# Peripherial_Bus.net
KiCad netlist of a schematic drawn in Altium Designer
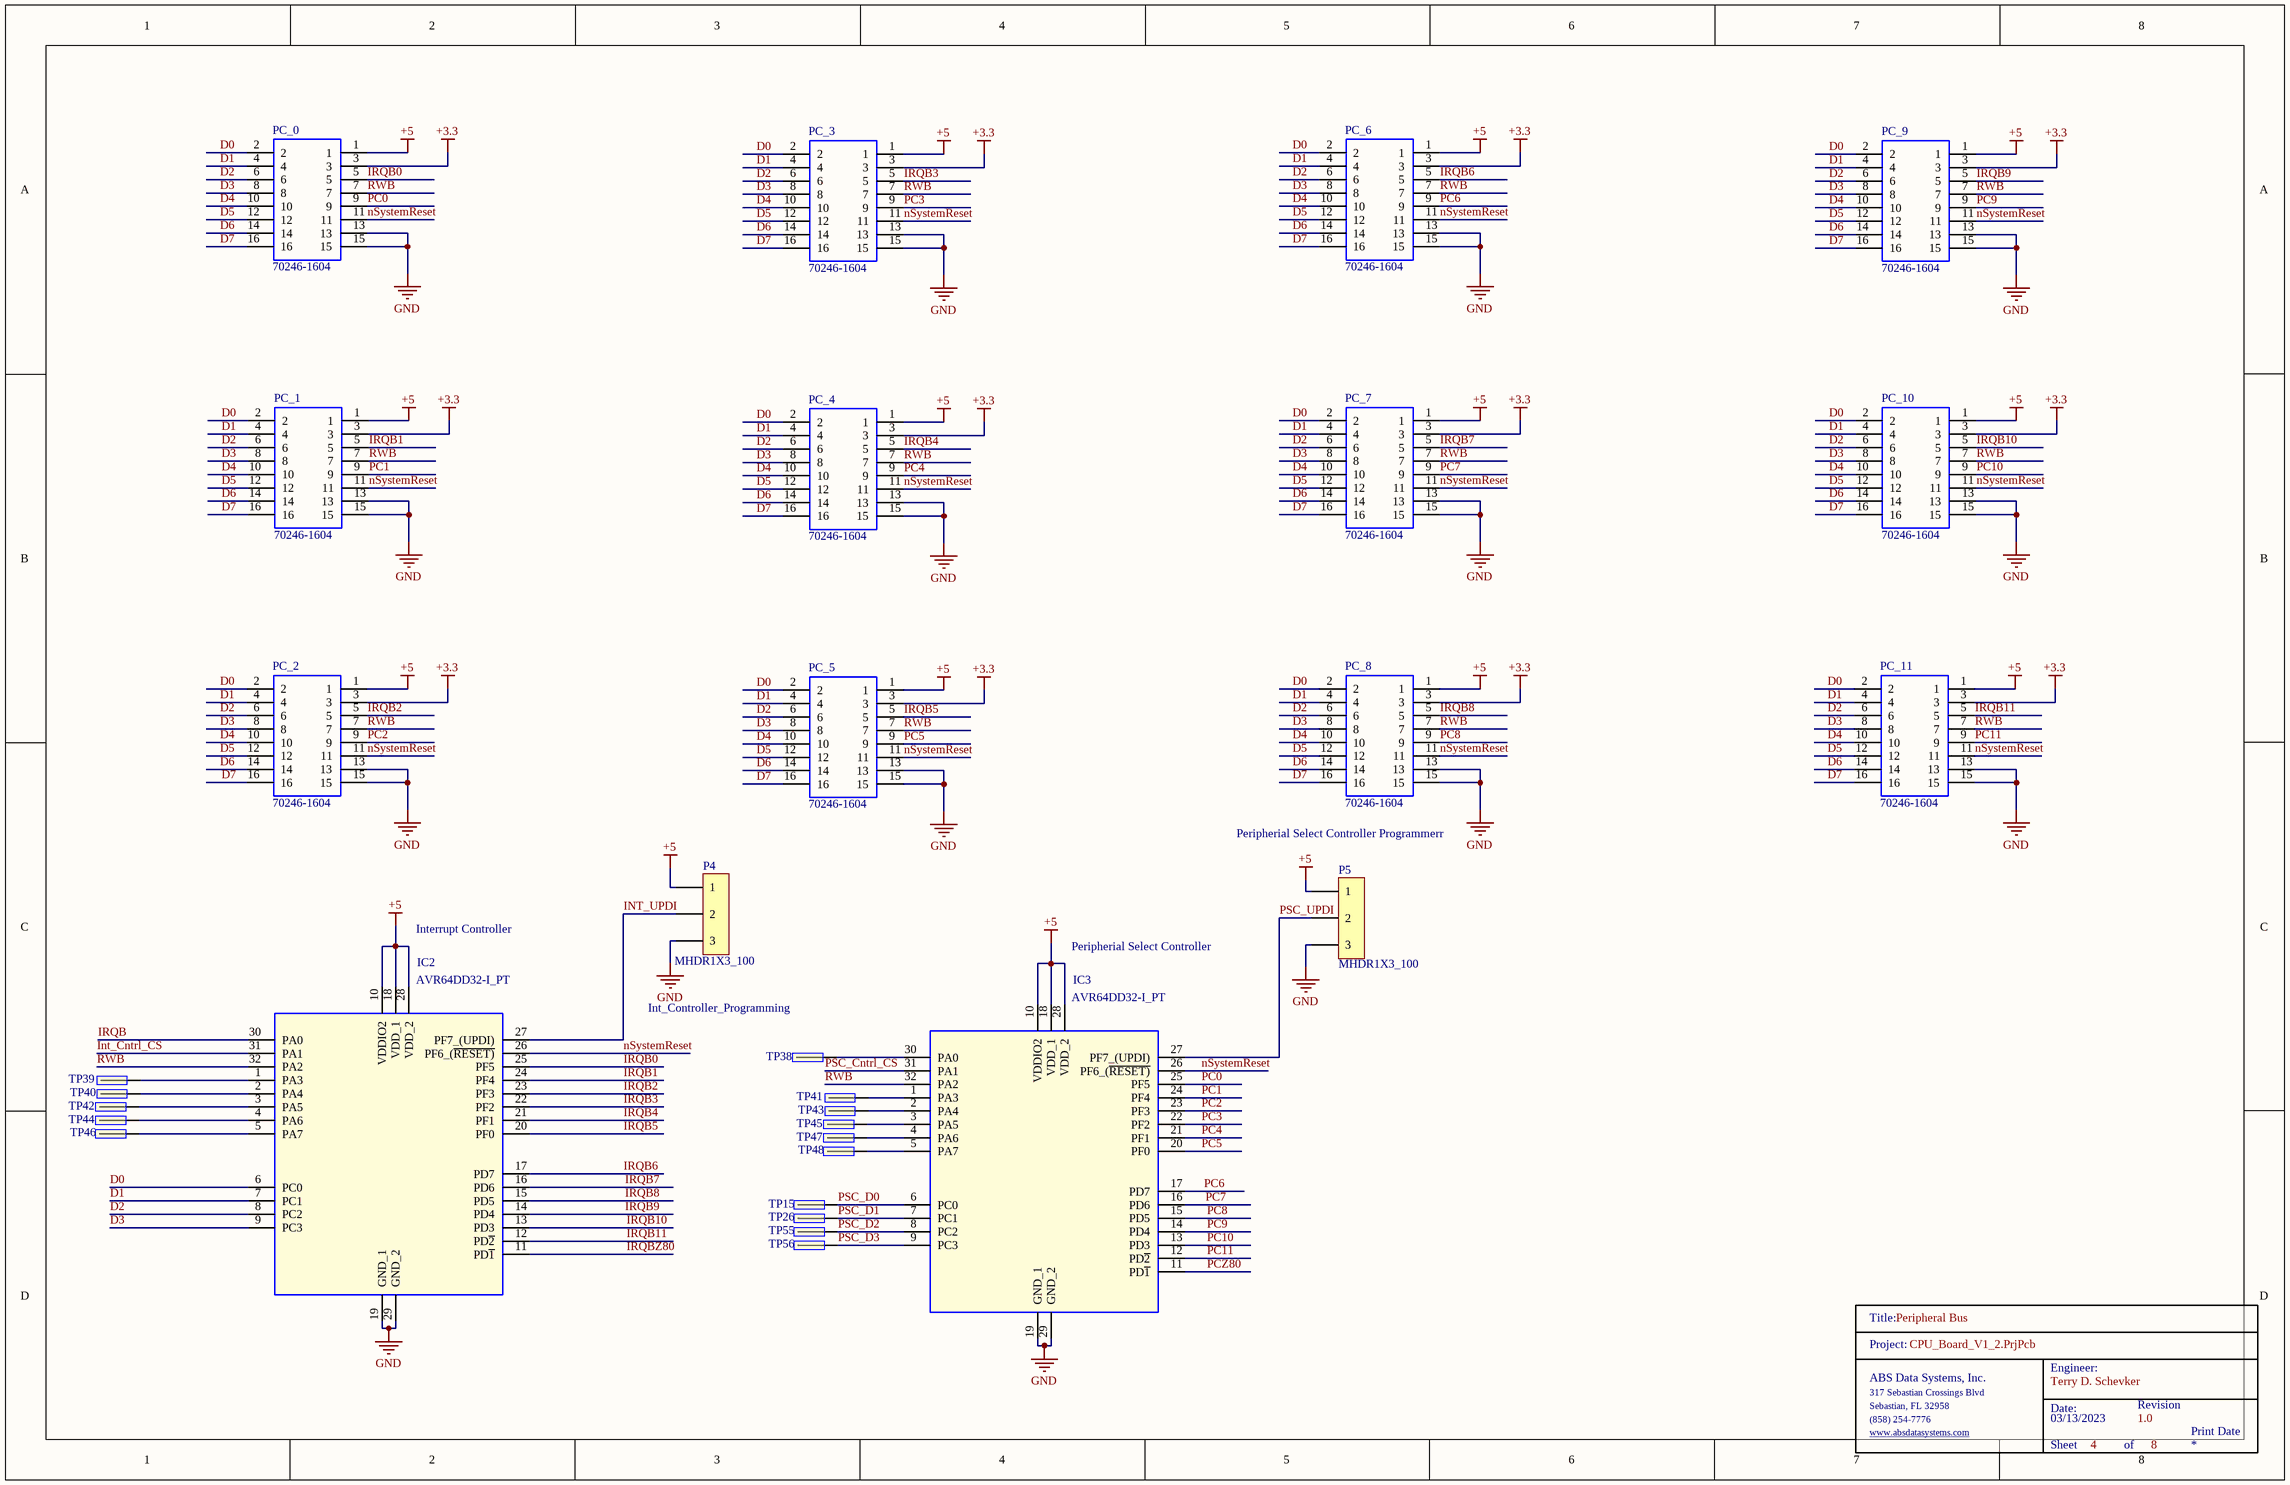
[diagram p0: Peripherial_Bus.SchDoc]

(export (version "E")
  (design (tool "Eeschema 10.0.6"))
  (components
    (comp (ref "IC2")
      (value "AVR64DD32-I_PT")
      (footprint "CPU_Memory:QFP80P900X900X120-32N")
      (description "Integrated Circuit")
      (fields (field (name "MANUFACTURER_PART_NUMBER") "AVR64DD32-I/PT ¦ MULTI-VOLTAGE I/O"))
      (libsource (lib "CPU_Memory") (part "AVR64DD32-I_PT"))
    )
    (comp (ref "IC3")
      (value "AVR64DD32-I_PT")
      (footprint "CPU_Memory:QFP80P900X900X120-32N")
      (description "Integrated Circuit")
      (fields (field (name "MANUFACTURER_PART_NUMBER") "AVR64DD32-I/PT ¦ MULTI-VOLTAGE I/O"))
      (libsource (lib "CPU_Memory") (part "AVR64DD32-I_PT"))
    )
    (comp (ref "P4")
      (value "MHDR1X3_100")
      (footprint "MHDR1X3_100")
      (description "Header, 3-Pin")
      (fields (field (name "PUBLISHER") "Altium Limited"))
      (libsource (lib "Connectors") (part "MHDR1X3_100"))
    )
    (comp (ref "P5")
      (value "MHDR1X3_100")
      (footprint "MHDR1X3_100")
      (description "Header, 3-Pin")
      (fields (field (name "PUBLISHER") "Altium Limited"))
      (libsource (lib "Connectors") (part "MHDR1X3_100"))
    )
    (comp (ref "PC_0")
      (value "70246-1604")
      (footprint "SHDR16W99P254_2X8_2794X889X927P")
      (description "Molex C-GRID 70246, 2.54mm Pitch, 16 Way, 2 Row, Straight PCB Header, Through Hole")
      (fields (field (name "MOUSER PART NUMBER") "538-70246-1604"))
      (libsource (lib "Connectors") (part "70246-1604"))
    )
    (comp (ref "PC_1")
      (value "70246-1604")
      (footprint "SHDR16W99P254_2X8_2794X889X927P")
      (description "Molex C-GRID 70246, 2.54mm Pitch, 16 Way, 2 Row, Straight PCB Header, Through Hole")
      (fields (field (name "MOUSER PART NUMBER") "538-70246-1604"))
      (libsource (lib "Connectors") (part "70246-1604"))
    )
    (comp (ref "PC_2")
      (value "70246-1604")
      (footprint "SHDR16W99P254_2X8_2794X889X927P")
      (description "Molex C-GRID 70246, 2.54mm Pitch, 16 Way, 2 Row, Straight PCB Header, Through Hole")
      (fields (field (name "MOUSER PART NUMBER") "538-70246-1604"))
      (libsource (lib "Connectors") (part "70246-1604"))
    )
    (comp (ref "PC_3")
      (value "70246-1604")
      (footprint "SHDR16W99P254_2X8_2794X889X927P")
      (description "Molex C-GRID 70246, 2.54mm Pitch, 16 Way, 2 Row, Straight PCB Header, Through Hole")
      (fields (field (name "MOUSER PART NUMBER") "538-70246-1604"))
      (libsource (lib "Connectors") (part "70246-1604"))
    )
    (comp (ref "PC_4")
      (value "70246-1604")
      (footprint "SHDR16W99P254_2X8_2794X889X927P")
      (description "Molex C-GRID 70246, 2.54mm Pitch, 16 Way, 2 Row, Straight PCB Header, Through Hole")
      (fields (field (name "MOUSER PART NUMBER") "538-70246-1604"))
      (libsource (lib "Connectors") (part "70246-1604"))
    )
    (comp (ref "PC_5")
      (value "70246-1604")
      (footprint "SHDR16W99P254_2X8_2794X889X927P")
      (description "Molex C-GRID 70246, 2.54mm Pitch, 16 Way, 2 Row, Straight PCB Header, Through Hole")
      (fields (field (name "MOUSER PART NUMBER") "538-70246-1604"))
      (libsource (lib "Connectors") (part "70246-1604"))
    )
    (comp (ref "PC_6")
      (value "70246-1604")
      (footprint "SHDR16W99P254_2X8_2794X889X927P")
      (description "Molex C-GRID 70246, 2.54mm Pitch, 16 Way, 2 Row, Straight PCB Header, Through Hole")
      (fields (field (name "MOUSER PART NUMBER") "538-70246-1604"))
      (libsource (lib "Connectors") (part "70246-1604"))
    )
    (comp (ref "PC_7")
      (value "70246-1604")
      (footprint "SHDR16W99P254_2X8_2794X889X927P")
      (description "Molex C-GRID 70246, 2.54mm Pitch, 16 Way, 2 Row, Straight PCB Header, Through Hole")
      (fields (field (name "MOUSER PART NUMBER") "538-70246-1604"))
      (libsource (lib "Connectors") (part "70246-1604"))
    )
    (comp (ref "PC_8")
      (value "70246-1604")
      (footprint "SHDR16W99P254_2X8_2794X889X927P")
      (description "Molex C-GRID 70246, 2.54mm Pitch, 16 Way, 2 Row, Straight PCB Header, Through Hole")
      (fields (field (name "MOUSER PART NUMBER") "538-70246-1604"))
      (libsource (lib "Connectors") (part "70246-1604"))
    )
    (comp (ref "PC_9")
      (value "70246-1604")
      (footprint "SHDR16W99P254_2X8_2794X889X927P")
      (description "Molex C-GRID 70246, 2.54mm Pitch, 16 Way, 2 Row, Straight PCB Header, Through Hole")
      (fields (field (name "MOUSER PART NUMBER") "538-70246-1604"))
      (libsource (lib "Connectors") (part "70246-1604"))
    )
    (comp (ref "PC_10")
      (value "70246-1604")
      (footprint "SHDR16W99P254_2X8_2794X889X927P")
      (description "Molex C-GRID 70246, 2.54mm Pitch, 16 Way, 2 Row, Straight PCB Header, Through Hole")
      (fields (field (name "MOUSER PART NUMBER") "538-70246-1604"))
      (libsource (lib "Connectors") (part "70246-1604"))
    )
    (comp (ref "PC_11")
      (value "70246-1604")
      (footprint "SHDR16W99P254_2X8_2794X889X927P")
      (description "Molex C-GRID 70246, 2.54mm Pitch, 16 Way, 2 Row, Straight PCB Header, Through Hole")
      (fields (field (name "MOUSER PART NUMBER") "538-70246-1604"))
      (libsource (lib "Connectors") (part "70246-1604"))
    )
    (comp (ref "TP15")
      (value "TP")
      (footprint "TP")
      (fields
        (field (name "MANUFACTURER") "Samtec")
        (field (name "MANUFACTURER PART NUMBER") "TST-105-01-G-D")
      )
      (libsource (lib "Misc") (part "TP"))
    )
    (comp (ref "TP26")
      (value "TP")
      (footprint "TP")
      (fields
        (field (name "MANUFACTURER") "Samtec")
        (field (name "MANUFACTURER PART NUMBER") "TST-105-01-G-D")
      )
      (libsource (lib "Misc") (part "TP"))
    )
    (comp (ref "TP38")
      (value "TP")
      (footprint "TP")
      (fields
        (field (name "MANUFACTURER") "Samtec")
        (field (name "MANUFACTURER PART NUMBER") "TST-105-01-G-D")
      )
      (libsource (lib "Misc") (part "TP"))
    )
    (comp (ref "TP39")
      (value "TP")
      (footprint "TP")
      (fields
        (field (name "MANUFACTURER") "Samtec")
        (field (name "MANUFACTURER PART NUMBER") "TST-105-01-G-D")
      )
      (libsource (lib "Misc") (part "TP"))
    )
    (comp (ref "TP40")
      (value "TP")
      (footprint "TP")
      (fields
        (field (name "MANUFACTURER") "Samtec")
        (field (name "MANUFACTURER PART NUMBER") "TST-105-01-G-D")
      )
      (libsource (lib "Misc") (part "TP"))
    )
    (comp (ref "TP41")
      (value "TP")
      (footprint "TP")
      (fields
        (field (name "MANUFACTURER") "Samtec")
        (field (name "MANUFACTURER PART NUMBER") "TST-105-01-G-D")
      )
      (libsource (lib "Misc") (part "TP"))
    )
    (comp (ref "TP42")
      (value "TP")
      (footprint "TP")
      (fields
        (field (name "MANUFACTURER") "Samtec")
        (field (name "MANUFACTURER PART NUMBER") "TST-105-01-G-D")
      )
      (libsource (lib "Misc") (part "TP"))
    )
    (comp (ref "TP43")
      (value "TP")
      (footprint "TP")
      (fields
        (field (name "MANUFACTURER") "Samtec")
        (field (name "MANUFACTURER PART NUMBER") "TST-105-01-G-D")
      )
      (libsource (lib "Misc") (part "TP"))
    )
    (comp (ref "TP44")
      (value "TP")
      (footprint "TP")
      (fields
        (field (name "MANUFACTURER") "Samtec")
        (field (name "MANUFACTURER PART NUMBER") "TST-105-01-G-D")
      )
      (libsource (lib "Misc") (part "TP"))
    )
    (comp (ref "TP45")
      (value "TP")
      (footprint "TP")
      (fields
        (field (name "MANUFACTURER") "Samtec")
        (field (name "MANUFACTURER PART NUMBER") "TST-105-01-G-D")
      )
      (libsource (lib "Misc") (part "TP"))
    )
    (comp (ref "TP46")
      (value "TP")
      (footprint "TP")
      (fields
        (field (name "MANUFACTURER") "Samtec")
        (field (name "MANUFACTURER PART NUMBER") "TST-105-01-G-D")
      )
      (libsource (lib "Misc") (part "TP"))
    )
    (comp (ref "TP47")
      (value "TP")
      (footprint "TP")
      (fields
        (field (name "MANUFACTURER") "Samtec")
        (field (name "MANUFACTURER PART NUMBER") "TST-105-01-G-D")
      )
      (libsource (lib "Misc") (part "TP"))
    )
    (comp (ref "TP48")
      (value "TP")
      (footprint "TP")
      (fields
        (field (name "MANUFACTURER") "Samtec")
        (field (name "MANUFACTURER PART NUMBER") "TST-105-01-G-D")
      )
      (libsource (lib "Misc") (part "TP"))
    )
    (comp (ref "TP55")
      (value "TP")
      (footprint "TP")
      (fields
        (field (name "MANUFACTURER") "Samtec")
        (field (name "MANUFACTURER PART NUMBER") "TST-105-01-G-D")
      )
      (libsource (lib "Misc") (part "TP"))
    )
    (comp (ref "TP56")
      (value "TP")
      (footprint "TP")
      (fields
        (field (name "MANUFACTURER") "Samtec")
        (field (name "MANUFACTURER PART NUMBER") "TST-105-01-G-D")
      )
      (libsource (lib "Misc") (part "TP"))
    )
  )
  (nets
    (net (code "1") (name "+3.3") (class "Default")
      (node (ref "PC_0") (pin "3") (pinfunction "3_3") (pintype "passive"))
      (node (ref "PC_1") (pin "3") (pinfunction "3_3") (pintype "passive"))
      (node (ref "PC_10") (pin "3") (pinfunction "3_3") (pintype "passive"))
      (node (ref "PC_11") (pin "3") (pinfunction "3_3") (pintype "passive"))
      (node (ref "PC_2") (pin "3") (pinfunction "3_3") (pintype "passive"))
      (node (ref "PC_3") (pin "3") (pinfunction "3_3") (pintype "passive"))
      (node (ref "PC_4") (pin "3") (pinfunction "3_3") (pintype "passive"))
      (node (ref "PC_5") (pin "3") (pinfunction "3_3") (pintype "passive"))
      (node (ref "PC_6") (pin "3") (pinfunction "3_3") (pintype "passive"))
      (node (ref "PC_7") (pin "3") (pinfunction "3_3") (pintype "passive"))
      (node (ref "PC_8") (pin "3") (pinfunction "3_3") (pintype "passive"))
      (node (ref "PC_9") (pin "3") (pinfunction "3_3") (pintype "passive"))
    )
    (net (code "2") (name "+5") (class "Default")
      (node (ref "IC2") (pin "10") (pinfunction "VDDIO2_10") (pintype "passive"))
      (node (ref "IC2") (pin "18") (pinfunction "VDD_1_18") (pintype "passive"))
      (node (ref "IC2") (pin "28") (pinfunction "VDD_2_28") (pintype "passive"))
      (node (ref "IC3") (pin "10") (pinfunction "VDDIO2_10") (pintype "passive"))
      (node (ref "IC3") (pin "18") (pinfunction "VDD_1_18") (pintype "passive"))
      (node (ref "IC3") (pin "28") (pinfunction "VDD_2_28") (pintype "passive"))
      (node (ref "P4") (pin "1") (pinfunction "1_1") (pintype "passive"))
      (node (ref "P5") (pin "1") (pinfunction "1_1") (pintype "passive"))
      (node (ref "PC_0") (pin "1") (pinfunction "1_1") (pintype "passive"))
      (node (ref "PC_1") (pin "1") (pinfunction "1_1") (pintype "passive"))
      (node (ref "PC_10") (pin "1") (pinfunction "1_1") (pintype "passive"))
      (node (ref "PC_11") (pin "1") (pinfunction "1_1") (pintype "passive"))
      (node (ref "PC_2") (pin "1") (pinfunction "1_1") (pintype "passive"))
      (node (ref "PC_3") (pin "1") (pinfunction "1_1") (pintype "passive"))
      (node (ref "PC_4") (pin "1") (pinfunction "1_1") (pintype "passive"))
      (node (ref "PC_5") (pin "1") (pinfunction "1_1") (pintype "passive"))
      (node (ref "PC_6") (pin "1") (pinfunction "1_1") (pintype "passive"))
      (node (ref "PC_7") (pin "1") (pinfunction "1_1") (pintype "passive"))
      (node (ref "PC_8") (pin "1") (pinfunction "1_1") (pintype "passive"))
      (node (ref "PC_9") (pin "1") (pinfunction "1_1") (pintype "passive"))
    )
    (net (code "3") (name "/D0") (class "Default")
      (node (ref "IC2") (pin "6") (pinfunction "PC0_6") (pintype "passive"))
      (node (ref "PC_0") (pin "2") (pinfunction "2_2") (pintype "passive"))
      (node (ref "PC_1") (pin "2") (pinfunction "2_2") (pintype "passive"))
      (node (ref "PC_10") (pin "2") (pinfunction "2_2") (pintype "passive"))
      (node (ref "PC_11") (pin "2") (pinfunction "2_2") (pintype "passive"))
      (node (ref "PC_2") (pin "2") (pinfunction "2_2") (pintype "passive"))
      (node (ref "PC_3") (pin "2") (pinfunction "2_2") (pintype "passive"))
      (node (ref "PC_4") (pin "2") (pinfunction "2_2") (pintype "passive"))
      (node (ref "PC_5") (pin "2") (pinfunction "2_2") (pintype "passive"))
      (node (ref "PC_6") (pin "2") (pinfunction "2_2") (pintype "passive"))
      (node (ref "PC_7") (pin "2") (pinfunction "2_2") (pintype "passive"))
      (node (ref "PC_8") (pin "2") (pinfunction "2_2") (pintype "passive"))
      (node (ref "PC_9") (pin "2") (pinfunction "2_2") (pintype "passive"))
    )
    (net (code "4") (name "/D1") (class "Default")
      (node (ref "IC2") (pin "7") (pinfunction "PC1_7") (pintype "passive"))
      (node (ref "PC_0") (pin "4") (pinfunction "4_4") (pintype "passive"))
      (node (ref "PC_1") (pin "4") (pinfunction "4_4") (pintype "passive"))
      (node (ref "PC_10") (pin "4") (pinfunction "4_4") (pintype "passive"))
      (node (ref "PC_11") (pin "4") (pinfunction "4_4") (pintype "passive"))
      (node (ref "PC_2") (pin "4") (pinfunction "4_4") (pintype "passive"))
      (node (ref "PC_3") (pin "4") (pinfunction "4_4") (pintype "passive"))
      (node (ref "PC_4") (pin "4") (pinfunction "4_4") (pintype "passive"))
      (node (ref "PC_5") (pin "4") (pinfunction "4_4") (pintype "passive"))
      (node (ref "PC_6") (pin "4") (pinfunction "4_4") (pintype "passive"))
      (node (ref "PC_7") (pin "4") (pinfunction "4_4") (pintype "passive"))
      (node (ref "PC_8") (pin "4") (pinfunction "4_4") (pintype "passive"))
      (node (ref "PC_9") (pin "4") (pinfunction "4_4") (pintype "passive"))
    )
    (net (code "5") (name "/D2") (class "Default")
      (node (ref "IC2") (pin "8") (pinfunction "PC2_8") (pintype "passive"))
      (node (ref "PC_0") (pin "6") (pinfunction "6_6") (pintype "passive"))
      (node (ref "PC_1") (pin "6") (pinfunction "6_6") (pintype "passive"))
      (node (ref "PC_10") (pin "6") (pinfunction "6_6") (pintype "passive"))
      (node (ref "PC_11") (pin "6") (pinfunction "6_6") (pintype "passive"))
      (node (ref "PC_2") (pin "6") (pinfunction "6_6") (pintype "passive"))
      (node (ref "PC_3") (pin "6") (pinfunction "6_6") (pintype "passive"))
      (node (ref "PC_4") (pin "6") (pinfunction "6_6") (pintype "passive"))
      (node (ref "PC_5") (pin "6") (pinfunction "6_6") (pintype "passive"))
      (node (ref "PC_6") (pin "6") (pinfunction "6_6") (pintype "passive"))
      (node (ref "PC_7") (pin "6") (pinfunction "6_6") (pintype "passive"))
      (node (ref "PC_8") (pin "6") (pinfunction "6_6") (pintype "passive"))
      (node (ref "PC_9") (pin "6") (pinfunction "6_6") (pintype "passive"))
    )
    (net (code "6") (name "/D3") (class "Default")
      (node (ref "IC2") (pin "9") (pinfunction "PC3_9") (pintype "passive"))
      (node (ref "PC_0") (pin "8") (pinfunction "8_8") (pintype "passive"))
      (node (ref "PC_1") (pin "8") (pinfunction "8_8") (pintype "passive"))
      (node (ref "PC_10") (pin "8") (pinfunction "8_8") (pintype "passive"))
      (node (ref "PC_11") (pin "8") (pinfunction "8_8") (pintype "passive"))
      (node (ref "PC_2") (pin "8") (pinfunction "8_8") (pintype "passive"))
      (node (ref "PC_3") (pin "8") (pinfunction "8_8") (pintype "passive"))
      (node (ref "PC_4") (pin "8") (pinfunction "8_8") (pintype "passive"))
      (node (ref "PC_5") (pin "8") (pinfunction "8_8") (pintype "passive"))
      (node (ref "PC_6") (pin "8") (pinfunction "8_8") (pintype "passive"))
      (node (ref "PC_7") (pin "8") (pinfunction "8_8") (pintype "passive"))
      (node (ref "PC_8") (pin "8") (pinfunction "8_8") (pintype "passive"))
      (node (ref "PC_9") (pin "8") (pinfunction "8_8") (pintype "passive"))
    )
    (net (code "7") (name "/D4") (class "Default")
      (node (ref "PC_0") (pin "10") (pinfunction "10_10") (pintype "passive"))
      (node (ref "PC_1") (pin "10") (pinfunction "10_10") (pintype "passive"))
      (node (ref "PC_10") (pin "10") (pinfunction "10_10") (pintype "passive"))
      (node (ref "PC_11") (pin "10") (pinfunction "10_10") (pintype "passive"))
      (node (ref "PC_2") (pin "10") (pinfunction "10_10") (pintype "passive"))
      (node (ref "PC_3") (pin "10") (pinfunction "10_10") (pintype "passive"))
      (node (ref "PC_4") (pin "10") (pinfunction "10_10") (pintype "passive"))
      (node (ref "PC_5") (pin "10") (pinfunction "10_10") (pintype "passive"))
      (node (ref "PC_6") (pin "10") (pinfunction "10_10") (pintype "passive"))
      (node (ref "PC_7") (pin "10") (pinfunction "10_10") (pintype "passive"))
      (node (ref "PC_8") (pin "10") (pinfunction "10_10") (pintype "passive"))
      (node (ref "PC_9") (pin "10") (pinfunction "10_10") (pintype "passive"))
    )
    (net (code "8") (name "/D5") (class "Default")
      (node (ref "PC_0") (pin "12") (pinfunction "12_12") (pintype "passive"))
      (node (ref "PC_1") (pin "12") (pinfunction "12_12") (pintype "passive"))
      (node (ref "PC_10") (pin "12") (pinfunction "12_12") (pintype "passive"))
      (node (ref "PC_11") (pin "12") (pinfunction "12_12") (pintype "passive"))
      (node (ref "PC_2") (pin "12") (pinfunction "12_12") (pintype "passive"))
      (node (ref "PC_3") (pin "12") (pinfunction "12_12") (pintype "passive"))
      (node (ref "PC_4") (pin "12") (pinfunction "12_12") (pintype "passive"))
      (node (ref "PC_5") (pin "12") (pinfunction "12_12") (pintype "passive"))
      (node (ref "PC_6") (pin "12") (pinfunction "12_12") (pintype "passive"))
      (node (ref "PC_7") (pin "12") (pinfunction "12_12") (pintype "passive"))
      (node (ref "PC_8") (pin "12") (pinfunction "12_12") (pintype "passive"))
      (node (ref "PC_9") (pin "12") (pinfunction "12_12") (pintype "passive"))
    )
    (net (code "9") (name "/D6") (class "Default")
      (node (ref "PC_0") (pin "14") (pinfunction "14_14") (pintype "passive"))
      (node (ref "PC_1") (pin "14") (pinfunction "14_14") (pintype "passive"))
      (node (ref "PC_10") (pin "14") (pinfunction "14_14") (pintype "passive"))
      (node (ref "PC_11") (pin "14") (pinfunction "14_14") (pintype "passive"))
      (node (ref "PC_2") (pin "14") (pinfunction "14_14") (pintype "passive"))
      (node (ref "PC_3") (pin "14") (pinfunction "14_14") (pintype "passive"))
      (node (ref "PC_4") (pin "14") (pinfunction "14_14") (pintype "passive"))
      (node (ref "PC_5") (pin "14") (pinfunction "14_14") (pintype "passive"))
      (node (ref "PC_6") (pin "14") (pinfunction "14_14") (pintype "passive"))
      (node (ref "PC_7") (pin "14") (pinfunction "14_14") (pintype "passive"))
      (node (ref "PC_8") (pin "14") (pinfunction "14_14") (pintype "passive"))
      (node (ref "PC_9") (pin "14") (pinfunction "14_14") (pintype "passive"))
    )
    (net (code "10") (name "/D7") (class "Default")
      (node (ref "PC_0") (pin "16") (pinfunction "16_16") (pintype "passive"))
      (node (ref "PC_1") (pin "16") (pinfunction "16_16") (pintype "passive"))
      (node (ref "PC_10") (pin "16") (pinfunction "16_16") (pintype "passive"))
      (node (ref "PC_11") (pin "16") (pinfunction "16_16") (pintype "passive"))
      (node (ref "PC_2") (pin "16") (pinfunction "16_16") (pintype "passive"))
      (node (ref "PC_3") (pin "16") (pinfunction "16_16") (pintype "passive"))
      (node (ref "PC_4") (pin "16") (pinfunction "16_16") (pintype "passive"))
      (node (ref "PC_5") (pin "16") (pinfunction "16_16") (pintype "passive"))
      (node (ref "PC_6") (pin "16") (pinfunction "16_16") (pintype "passive"))
      (node (ref "PC_7") (pin "16") (pinfunction "16_16") (pintype "passive"))
      (node (ref "PC_8") (pin "16") (pinfunction "16_16") (pintype "passive"))
      (node (ref "PC_9") (pin "16") (pinfunction "16_16") (pintype "passive"))
    )
    (net (code "11") (name "/INT_UPDI") (class "Default")
      (node (ref "IC2") (pin "27") (pinfunction "PF7_(UPDI)_27") (pintype "passive"))
      (node (ref "P4") (pin "2") (pinfunction "2_2") (pintype "passive"))
    )
    (net (code "12") (name "/IRQB") (class "Default")
      (node (ref "IC2") (pin "30") (pinfunction "PA0_30") (pintype "passive"))
    )
    (net (code "13") (name "/IRQB0") (class "Default")
      (node (ref "IC2") (pin "25") (pinfunction "PF5_25") (pintype "passive"))
      (node (ref "PC_0") (pin "5") (pinfunction "5_5") (pintype "passive"))
    )
    (net (code "14") (name "/IRQB1") (class "Default")
      (node (ref "IC2") (pin "24") (pinfunction "PF4_24") (pintype "passive"))
      (node (ref "PC_1") (pin "5") (pinfunction "5_5") (pintype "passive"))
    )
    (net (code "15") (name "/IRQB2") (class "Default")
      (node (ref "IC2") (pin "23") (pinfunction "PF3_23") (pintype "passive"))
      (node (ref "PC_2") (pin "5") (pinfunction "5_5") (pintype "passive"))
    )
    (net (code "16") (name "/IRQB3") (class "Default")
      (node (ref "IC2") (pin "22") (pinfunction "PF2_22") (pintype "passive"))
      (node (ref "PC_3") (pin "5") (pinfunction "5_5") (pintype "passive"))
    )
    (net (code "17") (name "/IRQB4") (class "Default")
      (node (ref "IC2") (pin "21") (pinfunction "PF1_21") (pintype "passive"))
      (node (ref "PC_4") (pin "5") (pinfunction "5_5") (pintype "passive"))
    )
    (net (code "18") (name "/IRQB5") (class "Default")
      (node (ref "IC2") (pin "20") (pinfunction "PF0_20") (pintype "passive"))
      (node (ref "PC_5") (pin "5") (pinfunction "5_5") (pintype "passive"))
    )
    (net (code "19") (name "/IRQB6") (class "Default")
      (node (ref "IC2") (pin "17") (pinfunction "PD7_17") (pintype "passive"))
      (node (ref "PC_6") (pin "5") (pinfunction "5_5") (pintype "passive"))
    )
    (net (code "20") (name "/IRQB7") (class "Default")
      (node (ref "IC2") (pin "16") (pinfunction "PD6_16") (pintype "passive"))
      (node (ref "PC_7") (pin "5") (pinfunction "5_5") (pintype "passive"))
    )
    (net (code "21") (name "/IRQB8") (class "Default")
      (node (ref "IC2") (pin "15") (pinfunction "PD5_15") (pintype "passive"))
      (node (ref "PC_8") (pin "5") (pinfunction "5_5") (pintype "passive"))
    )
    (net (code "22") (name "/IRQB9") (class "Default")
      (node (ref "IC2") (pin "14") (pinfunction "PD4_14") (pintype "passive"))
      (node (ref "PC_9") (pin "5") (pinfunction "5_5") (pintype "passive"))
    )
    (net (code "23") (name "/IRQB10") (class "Default")
      (node (ref "IC2") (pin "13") (pinfunction "PD3_13") (pintype "passive"))
      (node (ref "PC_10") (pin "5") (pinfunction "5_5") (pintype "passive"))
    )
    (net (code "24") (name "/IRQB11") (class "Default")
      (node (ref "IC2") (pin "12") (pinfunction "PD~{2}_12") (pintype "passive"))
      (node (ref "PC_11") (pin "5") (pinfunction "5_5") (pintype "passive"))
    )
    (net (code "25") (name "/IRQBZ80") (class "Default")
      (node (ref "IC2") (pin "11") (pinfunction "PD~{1}_11") (pintype "passive"))
    )
    (net (code "26") (name "/Int_Cntrl_CS") (class "Default")
      (node (ref "IC2") (pin "31") (pinfunction "PA1_31") (pintype "passive"))
    )
    (net (code "27") (name "/PC0") (class "Default")
      (node (ref "IC3") (pin "25") (pinfunction "PF5_25") (pintype "passive"))
      (node (ref "PC_0") (pin "9") (pinfunction "9_9") (pintype "passive"))
    )
    (net (code "28") (name "/PC1") (class "Default")
      (node (ref "IC3") (pin "24") (pinfunction "PF4_24") (pintype "passive"))
      (node (ref "PC_1") (pin "9") (pinfunction "9_9") (pintype "passive"))
    )
    (net (code "29") (name "/PC2") (class "Default")
      (node (ref "IC3") (pin "23") (pinfunction "PF3_23") (pintype "passive"))
      (node (ref "PC_2") (pin "9") (pinfunction "9_9") (pintype "passive"))
    )
    (net (code "30") (name "/PC3") (class "Default")
      (node (ref "IC3") (pin "22") (pinfunction "PF2_22") (pintype "passive"))
      (node (ref "PC_3") (pin "9") (pinfunction "9_9") (pintype "passive"))
    )
    (net (code "31") (name "/PC4") (class "Default")
      (node (ref "IC3") (pin "21") (pinfunction "PF1_21") (pintype "passive"))
      (node (ref "PC_4") (pin "9") (pinfunction "9_9") (pintype "passive"))
    )
    (net (code "32") (name "/PC5") (class "Default")
      (node (ref "IC3") (pin "20") (pinfunction "PF0_20") (pintype "passive"))
      (node (ref "PC_5") (pin "9") (pinfunction "9_9") (pintype "passive"))
    )
    (net (code "33") (name "/PC6") (class "Default")
      (node (ref "IC3") (pin "17") (pinfunction "PD7_17") (pintype "passive"))
      (node (ref "PC_6") (pin "9") (pinfunction "9_9") (pintype "passive"))
    )
    (net (code "34") (name "/PC7") (class "Default")
      (node (ref "IC3") (pin "16") (pinfunction "PD6_16") (pintype "passive"))
      (node (ref "PC_7") (pin "9") (pinfunction "9_9") (pintype "passive"))
    )
    (net (code "35") (name "/PC8") (class "Default")
      (node (ref "IC3") (pin "15") (pinfunction "PD5_15") (pintype "passive"))
      (node (ref "PC_8") (pin "9") (pinfunction "9_9") (pintype "passive"))
    )
    (net (code "36") (name "/PC9") (class "Default")
      (node (ref "IC3") (pin "14") (pinfunction "PD4_14") (pintype "passive"))
      (node (ref "PC_9") (pin "9") (pinfunction "9_9") (pintype "passive"))
    )
    (net (code "37") (name "/PC10") (class "Default")
      (node (ref "IC3") (pin "13") (pinfunction "PD3_13") (pintype "passive"))
      (node (ref "PC_10") (pin "9") (pinfunction "9_9") (pintype "passive"))
    )
    (net (code "38") (name "/PC11") (class "Default")
      (node (ref "IC3") (pin "12") (pinfunction "PD~{2}_12") (pintype "passive"))
      (node (ref "PC_11") (pin "9") (pinfunction "9_9") (pintype "passive"))
    )
    (net (code "39") (name "/PCZ80") (class "Default")
      (node (ref "IC3") (pin "11") (pinfunction "PD~{1}_11") (pintype "passive"))
    )
    (net (code "40") (name "/PSC_Cntrl_CS") (class "Default")
      (node (ref "IC3") (pin "31") (pinfunction "PA1_31") (pintype "passive"))
    )
    (net (code "41") (name "/PSC_D0") (class "Default")
      (node (ref "IC3") (pin "6") (pinfunction "PC0_6") (pintype "passive"))
      (node (ref "TP15") (pin "1") (pinfunction "1_1") (pintype "passive"))
    )
    (net (code "42") (name "/PSC_D1") (class "Default")
      (node (ref "IC3") (pin "7") (pinfunction "PC1_7") (pintype "passive"))
      (node (ref "TP26") (pin "1") (pinfunction "1_1") (pintype "passive"))
    )
    (net (code "43") (name "/PSC_D2") (class "Default")
      (node (ref "IC3") (pin "8") (pinfunction "PC2_8") (pintype "passive"))
      (node (ref "TP55") (pin "1") (pinfunction "1_1") (pintype "passive"))
    )
    (net (code "44") (name "/PSC_D3") (class "Default")
      (node (ref "IC3") (pin "9") (pinfunction "PC3_9") (pintype "passive"))
      (node (ref "TP56") (pin "1") (pinfunction "1_1") (pintype "passive"))
    )
    (net (code "45") (name "/PSC_UPDI") (class "Default")
      (node (ref "IC3") (pin "27") (pinfunction "PF7_(UPDI)_27") (pintype "passive"))
      (node (ref "P5") (pin "2") (pinfunction "2_2") (pintype "passive"))
    )
    (net (code "46") (name "/RWB") (class "Default")
      (node (ref "IC2") (pin "32") (pinfunction "PA2_32") (pintype "passive"))
      (node (ref "IC3") (pin "32") (pinfunction "PA2_32") (pintype "passive"))
      (node (ref "PC_0") (pin "7") (pinfunction "7_7") (pintype "passive"))
      (node (ref "PC_1") (pin "7") (pinfunction "7_7") (pintype "passive"))
      (node (ref "PC_10") (pin "7") (pinfunction "7_7") (pintype "passive"))
      (node (ref "PC_11") (pin "7") (pinfunction "7_7") (pintype "passive"))
      (node (ref "PC_2") (pin "7") (pinfunction "7_7") (pintype "passive"))
      (node (ref "PC_3") (pin "7") (pinfunction "7_7") (pintype "passive"))
      (node (ref "PC_4") (pin "7") (pinfunction "7_7") (pintype "passive"))
      (node (ref "PC_5") (pin "7") (pinfunction "7_7") (pintype "passive"))
      (node (ref "PC_6") (pin "7") (pinfunction "7_7") (pintype "passive"))
      (node (ref "PC_7") (pin "7") (pinfunction "7_7") (pintype "passive"))
      (node (ref "PC_8") (pin "7") (pinfunction "7_7") (pintype "passive"))
      (node (ref "PC_9") (pin "7") (pinfunction "7_7") (pintype "passive"))
    )
    (net (code "47") (name "/nSystemReset") (class "Default")
      (node (ref "IC2") (pin "26") (pinfunction "PF6_(~{RESET)}_26") (pintype "passive"))
      (node (ref "IC3") (pin "26") (pinfunction "PF6_(~{RESET)}_26") (pintype "passive"))
      (node (ref "PC_0") (pin "11") (pinfunction "11_11") (pintype "passive"))
      (node (ref "PC_1") (pin "11") (pinfunction "11_11") (pintype "passive"))
      (node (ref "PC_10") (pin "11") (pinfunction "11_11") (pintype "passive"))
      (node (ref "PC_11") (pin "11") (pinfunction "11_11") (pintype "passive"))
      (node (ref "PC_2") (pin "11") (pinfunction "11_11") (pintype "passive"))
      (node (ref "PC_3") (pin "11") (pinfunction "11_11") (pintype "passive"))
      (node (ref "PC_4") (pin "11") (pinfunction "11_11") (pintype "passive"))
      (node (ref "PC_5") (pin "11") (pinfunction "11_11") (pintype "passive"))
      (node (ref "PC_6") (pin "11") (pinfunction "11_11") (pintype "passive"))
      (node (ref "PC_7") (pin "11") (pinfunction "11_11") (pintype "passive"))
      (node (ref "PC_8") (pin "11") (pinfunction "11_11") (pintype "passive"))
      (node (ref "PC_9") (pin "11") (pinfunction "11_11") (pintype "passive"))
    )
    (net (code "48") (name "GND") (class "Default")
      (node (ref "IC2") (pin "19") (pinfunction "GND_1_19") (pintype "passive"))
      (node (ref "IC2") (pin "29") (pinfunction "GND_2_29") (pintype "passive"))
      (node (ref "IC3") (pin "19") (pinfunction "GND_1_19") (pintype "passive"))
      (node (ref "IC3") (pin "29") (pinfunction "GND_2_29") (pintype "passive"))
      (node (ref "P4") (pin "3") (pinfunction "3_3") (pintype "passive"))
      (node (ref "P5") (pin "3") (pinfunction "3_3") (pintype "passive"))
      (node (ref "PC_0") (pin "13") (pinfunction "13_13") (pintype "passive"))
      (node (ref "PC_0") (pin "15") (pinfunction "15_15") (pintype "passive"))
      (node (ref "PC_1") (pin "13") (pinfunction "13_13") (pintype "passive"))
      (node (ref "PC_1") (pin "15") (pinfunction "15_15") (pintype "passive"))
      (node (ref "PC_10") (pin "13") (pinfunction "13_13") (pintype "passive"))
      (node (ref "PC_10") (pin "15") (pinfunction "15_15") (pintype "passive"))
      (node (ref "PC_11") (pin "13") (pinfunction "13_13") (pintype "passive"))
      (node (ref "PC_11") (pin "15") (pinfunction "15_15") (pintype "passive"))
      (node (ref "PC_2") (pin "13") (pinfunction "13_13") (pintype "passive"))
      (node (ref "PC_2") (pin "15") (pinfunction "15_15") (pintype "passive"))
      (node (ref "PC_3") (pin "13") (pinfunction "13_13") (pintype "passive"))
      (node (ref "PC_3") (pin "15") (pinfunction "15_15") (pintype "passive"))
      (node (ref "PC_4") (pin "13") (pinfunction "13_13") (pintype "passive"))
      (node (ref "PC_4") (pin "15") (pinfunction "15_15") (pintype "passive"))
      (node (ref "PC_5") (pin "13") (pinfunction "13_13") (pintype "passive"))
      (node (ref "PC_5") (pin "15") (pinfunction "15_15") (pintype "passive"))
      (node (ref "PC_6") (pin "13") (pinfunction "13_13") (pintype "passive"))
      (node (ref "PC_6") (pin "15") (pinfunction "15_15") (pintype "passive"))
      (node (ref "PC_7") (pin "13") (pinfunction "13_13") (pintype "passive"))
      (node (ref "PC_7") (pin "15") (pinfunction "15_15") (pintype "passive"))
      (node (ref "PC_8") (pin "13") (pinfunction "13_13") (pintype "passive"))
      (node (ref "PC_8") (pin "15") (pinfunction "15_15") (pintype "passive"))
      (node (ref "PC_9") (pin "13") (pinfunction "13_13") (pintype "passive"))
      (node (ref "PC_9") (pin "15") (pinfunction "15_15") (pintype "passive"))
    )
    (net (code "49") (name "Net-(IC2-PA3)") (class "Default")
      (node (ref "IC2") (pin "1") (pinfunction "PA3_1") (pintype "passive"))
      (node (ref "TP39") (pin "1") (pinfunction "1_1") (pintype "passive"))
    )
    (net (code "50") (name "Net-(IC2-PA4)") (class "Default")
      (node (ref "IC2") (pin "2") (pinfunction "PA4_2") (pintype "passive"))
      (node (ref "TP40") (pin "1") (pinfunction "1_1") (pintype "passive"))
    )
    (net (code "51") (name "Net-(IC2-PA5)") (class "Default")
      (node (ref "IC2") (pin "3") (pinfunction "PA5_3") (pintype "passive"))
      (node (ref "TP42") (pin "1") (pinfunction "1_1") (pintype "passive"))
    )
    (net (code "52") (name "Net-(IC2-PA6)") (class "Default")
      (node (ref "IC2") (pin "4") (pinfunction "PA6_4") (pintype "passive"))
      (node (ref "TP44") (pin "1") (pinfunction "1_1") (pintype "passive"))
    )
    (net (code "53") (name "Net-(IC2-PA7)") (class "Default")
      (node (ref "IC2") (pin "5") (pinfunction "PA7_5") (pintype "passive"))
      (node (ref "TP46") (pin "1") (pinfunction "1_1") (pintype "passive"))
    )
    (net (code "54") (name "Net-(IC3-PA0)") (class "Default")
      (node (ref "IC3") (pin "30") (pinfunction "PA0_30") (pintype "passive"))
      (node (ref "TP38") (pin "1") (pinfunction "1_1") (pintype "passive"))
    )
    (net (code "55") (name "Net-(IC3-PA3)") (class "Default")
      (node (ref "IC3") (pin "1") (pinfunction "PA3_1") (pintype "passive"))
      (node (ref "TP41") (pin "1") (pinfunction "1_1") (pintype "passive"))
    )
    (net (code "56") (name "Net-(IC3-PA4)") (class "Default")
      (node (ref "IC3") (pin "2") (pinfunction "PA4_2") (pintype "passive"))
      (node (ref "TP43") (pin "1") (pinfunction "1_1") (pintype "passive"))
    )
    (net (code "57") (name "Net-(IC3-PA5)") (class "Default")
      (node (ref "IC3") (pin "3") (pinfunction "PA5_3") (pintype "passive"))
      (node (ref "TP45") (pin "1") (pinfunction "1_1") (pintype "passive"))
    )
    (net (code "58") (name "Net-(IC3-PA6)") (class "Default")
      (node (ref "IC3") (pin "4") (pinfunction "PA6_4") (pintype "passive"))
      (node (ref "TP47") (pin "1") (pinfunction "1_1") (pintype "passive"))
    )
    (net (code "59") (name "Net-(IC3-PA7)") (class "Default")
      (node (ref "IC3") (pin "5") (pinfunction "PA7_5") (pintype "passive"))
      (node (ref "TP48") (pin "1") (pinfunction "1_1") (pintype "passive"))
    )
  )
)
